# baskettarget_V2.net
KiCad netlist of a schematic drawn in EAGLE
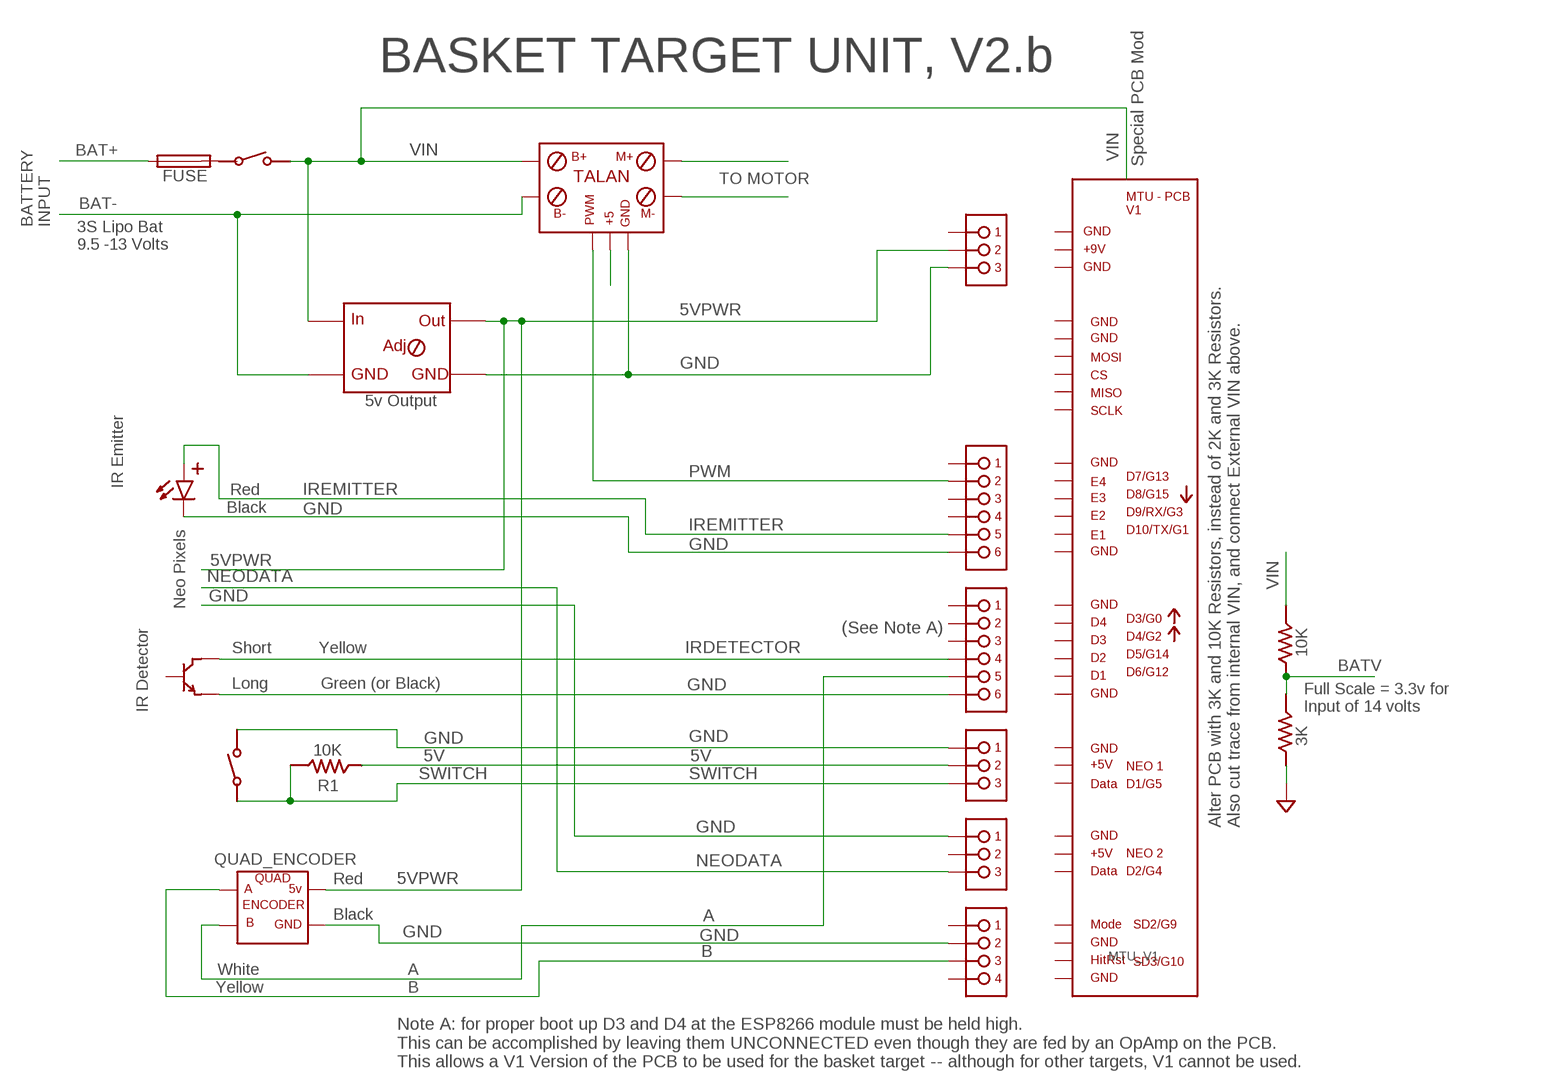
[diagram p0: schematic, sheet 1]

(export (version "E")
  (design (tool "Eeschema 10.0.6"))
  (components
    (comp (ref "F2")
      (value "FUSE")
      (footprint "eagle-import:FUSE_HOLDER_WICKMANN-19596")
      (libsource (lib "eagle-import") (part "FUSE19596"))
    )
    (comp (ref "J1")
      (value "ENCODER")
      (footprint "eagle-import:PINHDR_TH_100_1X4")
      (libsource (lib "eagle-import") (part "PINHDR_1X4TH_VERT_100"))
    )
    (comp (ref "J2")
      (value "NEO")
      (footprint "eagle-import:PINHDR_TH_100_1X3")
      (libsource (lib "eagle-import") (part "PINHDR_1X3-100"))
    )
    (comp (ref "J4")
      (value "INPUTS")
      (footprint "eagle-import:PINHDR_TH_100_1X6")
      (libsource (lib "eagle-import") (part "PINHDR_1X6-100"))
    )
    (comp (ref "J6")
      (value "OUTPUTS")
      (footprint "eagle-import:PINHDR_TH_100_1X6")
      (libsource (lib "eagle-import") (part "PINHDR_1X6-100"))
    )
    (comp (ref "J7")
      (value "PWR")
      (footprint "eagle-import:PINHDR_TH_100_1X3")
      (libsource (lib "eagle-import") (part "PINHDR_1X3-100"))
    )
    (comp (ref "J10")
      (value "SERVO")
      (footprint "eagle-import:PINHDR_TH_100_1X3")
      (libsource (lib "eagle-import") (part "PINHDR_1X3-100"))
    )
    (comp (ref "LED1")
      (value "IR Emitter")
      (footprint "eagle-import:LED-TH100")
      (libsource (lib "eagle-import") (part "LEDTH-DIP-100"))
    )
    (comp (ref "M1")
      (value "MTU_V1")
      (footprint "eagle-import:MTU_V1")
      (libsource (lib "eagle-import") (part "MTU_V1"))
    )
    (comp (ref "M2")
      (value "TALAN")
      (footprint "eagle-import:TALAN_PWM")
      (libsource (lib "eagle-import") (part "TALAN"))
    )
    (comp (ref "M4")
      (value "5v Output")
      (footprint "eagle-import:DC_DC_MODULE")
      (libsource (lib "eagle-import") (part "DC_DC_MODULE"))
    )
    (comp (ref "R1")
      (value "10K")
      (footprint "eagle-import:R300")
      (libsource (lib "eagle-import") (part "RTHOLE300"))
    )
    (comp (ref "R10")
      (value "10K")
      (footprint "eagle-import:R300")
      (libsource (lib "eagle-import") (part "RTHOLE300"))
    )
    (comp (ref "R11")
      (value "3K")
      (footprint "eagle-import:R300")
      (libsource (lib "eagle-import") (part "RTHOLE300"))
    )
    (comp (ref "S1")
      (value "TOGGLE_SPST")
      (footprint "eagle-import:SPST_TOGGLE")
      (libsource (lib "eagle-import") (part "TOGGLE_SPST"))
    )
    (comp (ref "S2")
      (value "TOGGLE_SPST")
      (footprint "eagle-import:SPST_TOGGLE")
      (libsource (lib "eagle-import") (part "TOGGLE_SPST"))
    )
    (comp (ref "T1")
      (value "T_NPN")
      (footprint "eagle-import:TO-92")
      (libsource (lib "eagle-import") (part "T_NPN"))
    )
    (comp (ref "U2")
      (value "QUAD_ENCODER")
      (footprint "eagle-import:QUAD_ENCODER")
      (libsource (lib "eagle-import") (part "QUAD_ENCODER"))
    )
  )
  (nets
    (net (code "1") (name "/5V") (class "Default")
      (node (ref "J2") (pin "2") (pinfunction "2_2") (pintype "passive"))
      (node (ref "R1") (pin "P$1") (pinfunction "1_P$1") (pintype "passive"))
    )
    (net (code "2") (name "/5VPWR") (class "Default")
      (node (ref "J7") (pin "2") (pinfunction "2_2") (pintype "passive"))
      (node (ref "M4") (pin "OUT+") (pinfunction "OUT_OUT+") (pintype "passive"))
      (node (ref "U2") (pin "5V") (pinfunction "5V_5V") (pintype "passive"))
    )
    (net (code "3") (name "/A") (class "Default")
      (node (ref "J4") (pin "5") (pinfunction "5_5") (pintype "passive"))
      (node (ref "U2") (pin "B") (pinfunction "B_B") (pintype "passive"))
    )
    (net (code "4") (name "/B") (class "Default")
      (node (ref "J1") (pin "3") (pinfunction "3_3") (pintype "passive"))
      (node (ref "U2") (pin "A") (pinfunction "A_A") (pintype "passive"))
    )
    (net (code "5") (name "/BAT+") (class "Default")
      (node (ref "F2") (pin "A") (pinfunction "1_A") (pintype "passive"))
    )
    (net (code "6") (name "/BAT-") (class "Default")
      (node (ref "M2") (pin "B-") (pinfunction "B-_B-") (pintype "passive"))
      (node (ref "M4") (pin "IN-") (pinfunction "G1_IN-") (pintype "passive"))
    )
    (net (code "7") (name "/BATV") (class "Default")
      (node (ref "R10") (pin "P$1") (pinfunction "1_P$1") (pintype "passive"))
      (node (ref "R11") (pin "P$2") (pinfunction "2_P$2") (pintype "passive"))
    )
    (net (code "8") (name "/IRDETECTOR") (class "Default")
      (node (ref "J4") (pin "4") (pinfunction "4_4") (pintype "passive"))
      (node (ref "T1") (pin "P$1") (pinfunction "COLLECTOR_P$1") (pintype "passive"))
    )
    (net (code "9") (name "/IREMITTER") (class "Default")
      (node (ref "J6") (pin "5") (pinfunction "5_5") (pintype "passive"))
      (node (ref "LED1") (pin "P$1") (pinfunction "ANODE_P$1") (pintype "passive"))
    )
    (net (code "10") (name "/NEODATA") (class "Default")
      (node (ref "J10") (pin "3") (pinfunction "3_3") (pintype "passive"))
    )
    (net (code "11") (name "/PWM") (class "Default")
      (node (ref "J6") (pin "2") (pinfunction "2_2") (pintype "passive"))
      (node (ref "M2") (pin "PWM") (pinfunction "PWM_PWM") (pintype "passive"))
    )
    (net (code "12") (name "/SWITCH") (class "Default")
      (node (ref "J2") (pin "3") (pinfunction "3_3") (pintype "passive"))
      (node (ref "R1") (pin "P$2") (pinfunction "2_P$2") (pintype "passive"))
      (node (ref "S1") (pin "P$1") (pinfunction "P$1_P$1") (pintype "passive"))
    )
    (net (code "13") (name "/VIN") (class "Default")
      (node (ref "M2") (pin "B+") (pinfunction "B+_B+") (pintype "passive"))
      (node (ref "M4") (pin "IN+") (pinfunction "IN_IN+") (pintype "passive"))
      (node (ref "R10") (pin "P$2") (pinfunction "2_P$2") (pintype "passive"))
      (node (ref "S2") (pin "P$2") (pinfunction "P$2_P$2") (pintype "passive"))
    )
    (net (code "14") (name "GND") (class "Default")
      (node (ref "J1") (pin "2") (pinfunction "2_2") (pintype "passive"))
      (node (ref "J10") (pin "1") (pinfunction "1_1") (pintype "passive"))
      (node (ref "J2") (pin "1") (pinfunction "1_1") (pintype "passive"))
      (node (ref "J4") (pin "6") (pinfunction "6_6") (pintype "passive"))
      (node (ref "J6") (pin "6") (pinfunction "6_6") (pintype "passive"))
      (node (ref "J7") (pin "3") (pinfunction "3_3") (pintype "passive"))
      (node (ref "LED1") (pin "P$2") (pinfunction "CATHODE_P$2") (pintype "passive"))
      (node (ref "M2") (pin "GND") (pinfunction "GND_GND") (pintype "passive"))
      (node (ref "M4") (pin "OUT-") (pinfunction "G2_OUT-") (pintype "passive"))
      (node (ref "R11") (pin "P$1") (pinfunction "1_P$1") (pintype "passive"))
      (node (ref "S1") (pin "P$2") (pinfunction "P$2_P$2") (pintype "passive"))
      (node (ref "T1") (pin "P$3") (pinfunction "EMITTER_P$3") (pintype "passive"))
      (node (ref "U2") (pin "GND") (pinfunction "GND_GND") (pintype "passive"))
    )
    (net (code "15") (name "Net-(F2-2)") (class "Default")
      (node (ref "F2") (pin "B") (pinfunction "2_B") (pintype "passive"))
      (node (ref "S2") (pin "P$1") (pinfunction "P$1_P$1") (pintype "passive"))
    )
    (net (code "16") (name "unconnected-(J1-Pad1)") (class "Default")
      (node (ref "J1") (pin "1") (pinfunction "1_1") (pintype "passive"))
    )
    (net (code "17") (name "unconnected-(J1-Pad4)") (class "Default")
      (node (ref "J1") (pin "4") (pinfunction "4_4") (pintype "passive"))
    )
    (net (code "18") (name "unconnected-(J4-Pad1)") (class "Default")
      (node (ref "J4") (pin "1") (pinfunction "1_1") (pintype "passive"))
    )
    (net (code "19") (name "unconnected-(J4-Pad2)") (class "Default")
      (node (ref "J4") (pin "2") (pinfunction "2_2") (pintype "passive"))
    )
    (net (code "20") (name "unconnected-(J4-Pad3)") (class "Default")
      (node (ref "J4") (pin "3") (pinfunction "3_3") (pintype "passive"))
    )
    (net (code "21") (name "unconnected-(J6-Pad1)") (class "Default")
      (node (ref "J6") (pin "1") (pinfunction "1_1") (pintype "passive"))
    )
    (net (code "22") (name "unconnected-(J6-Pad3)") (class "Default")
      (node (ref "J6") (pin "3") (pinfunction "3_3") (pintype "passive"))
    )
    (net (code "23") (name "unconnected-(J6-Pad4)") (class "Default")
      (node (ref "J6") (pin "4") (pinfunction "4_4") (pintype "passive"))
    )
    (net (code "24") (name "unconnected-(J7-Pad1)") (class "Default")
      (node (ref "J7") (pin "1") (pinfunction "1_1") (pintype "passive"))
    )
    (net (code "25") (name "unconnected-(J10-Pad2)") (class "Default")
      (node (ref "J10") (pin "2") (pinfunction "2_2") (pintype "passive"))
    )
    (net (code "26") (name "unconnected-(M1-PadP$1)") (class "Default")
      (node (ref "M1") (pin "P$1") (pinfunction "P$1_P$1") (pintype "bidirectional"))
    )
    (net (code "27") (name "unconnected-(M1-PadP$2)") (class "Default")
      (node (ref "M1") (pin "P$2") (pinfunction "P$2_P$2") (pintype "bidirectional"))
    )
    (net (code "28") (name "unconnected-(M1-PadP$3)") (class "Default")
      (node (ref "M1") (pin "P$3") (pinfunction "P$3_P$3") (pintype "bidirectional"))
    )
    (net (code "29") (name "unconnected-(M1-PadP$4)") (class "Default")
      (node (ref "M1") (pin "P$4") (pinfunction "P$4_P$4") (pintype "bidirectional"))
    )
    (net (code "30") (name "unconnected-(M1-PadP$5)") (class "Default")
      (node (ref "M1") (pin "P$5") (pinfunction "P$5_P$5") (pintype "bidirectional"))
    )
    (net (code "31") (name "unconnected-(M1-PadP$6)") (class "Default")
      (node (ref "M1") (pin "P$6") (pinfunction "P$6_P$6") (pintype "bidirectional"))
    )
    (net (code "32") (name "unconnected-(M1-PadP$7)") (class "Default")
      (node (ref "M1") (pin "P$7") (pinfunction "P$7_P$7") (pintype "bidirectional"))
    )
    (net (code "33") (name "unconnected-(M1-PadP$8)") (class "Default")
      (node (ref "M1") (pin "P$8") (pinfunction "P$8_P$8") (pintype "bidirectional"))
    )
    (net (code "34") (name "unconnected-(M1-PadP$9)") (class "Default")
      (node (ref "M1") (pin "P$9") (pinfunction "P$9_P$9") (pintype "bidirectional"))
    )
    (net (code "35") (name "unconnected-(M1-PadP$10)") (class "Default")
      (node (ref "M1") (pin "P$10") (pinfunction "P$10_P$10") (pintype "bidirectional"))
    )
    (net (code "36") (name "unconnected-(M1-PadP$11)") (class "Default")
      (node (ref "M1") (pin "P$11") (pinfunction "P$11_P$11") (pintype "bidirectional"))
    )
    (net (code "37") (name "unconnected-(M1-PadP$12)") (class "Default")
      (node (ref "M1") (pin "P$12") (pinfunction "P$12_P$12") (pintype "bidirectional"))
    )
    (net (code "38") (name "unconnected-(M1-PadP$13)") (class "Default")
      (node (ref "M1") (pin "P$13") (pinfunction "P$13_P$13") (pintype "bidirectional"))
    )
    (net (code "39") (name "unconnected-(M1-PadP$14)") (class "Default")
      (node (ref "M1") (pin "P$14") (pinfunction "P$14_P$14") (pintype "bidirectional"))
    )
    (net (code "40") (name "unconnected-(M1-PadP$15)") (class "Default")
      (node (ref "M1") (pin "P$15") (pinfunction "P$15_P$15") (pintype "bidirectional"))
    )
    (net (code "41") (name "unconnected-(M1-PadP$16)") (class "Default")
      (node (ref "M1") (pin "P$16") (pinfunction "P$16_P$16") (pintype "bidirectional"))
    )
    (net (code "42") (name "unconnected-(M1-PadP$17)") (class "Default")
      (node (ref "M1") (pin "P$17") (pinfunction "P$17_P$17") (pintype "bidirectional"))
    )
    (net (code "43") (name "unconnected-(M1-PadP$18)") (class "Default")
      (node (ref "M1") (pin "P$18") (pinfunction "P$18_P$18") (pintype "bidirectional"))
    )
    (net (code "44") (name "unconnected-(M1-PadP$19)") (class "Default")
      (node (ref "M1") (pin "P$19") (pinfunction "P$19_P$19") (pintype "bidirectional"))
    )
    (net (code "45") (name "unconnected-(M1-PadP$20)") (class "Default")
      (node (ref "M1") (pin "P$20") (pinfunction "P$20_P$20") (pintype "bidirectional"))
    )
    (net (code "46") (name "unconnected-(M1-PadP$21)") (class "Default")
      (node (ref "M1") (pin "P$21") (pinfunction "P$21_P$21") (pintype "bidirectional"))
    )
    (net (code "47") (name "unconnected-(M1-PadP$22)") (class "Default")
      (node (ref "M1") (pin "P$22") (pinfunction "P$22_P$22") (pintype "bidirectional"))
    )
    (net (code "48") (name "unconnected-(M1-PadP$23)") (class "Default")
      (node (ref "M1") (pin "P$23") (pinfunction "P$23_P$23") (pintype "bidirectional"))
    )
    (net (code "49") (name "unconnected-(M1-PadP$24)") (class "Default")
      (node (ref "M1") (pin "P$24") (pinfunction "P$24_P$24") (pintype "bidirectional"))
    )
    (net (code "50") (name "unconnected-(M1-PadP$25)") (class "Default")
      (node (ref "M1") (pin "P$25") (pinfunction "P$25_P$25") (pintype "bidirectional"))
    )
    (net (code "51") (name "unconnected-(M1-PadP$26)") (class "Default")
      (node (ref "M1") (pin "P$26") (pinfunction "P$26_P$26") (pintype "bidirectional"))
    )
    (net (code "52") (name "unconnected-(M1-PadP$27)") (class "Default")
      (node (ref "M1") (pin "P$27") (pinfunction "P$27_P$27") (pintype "bidirectional"))
    )
    (net (code "53") (name "unconnected-(M1-PadP$28)") (class "Default")
      (node (ref "M1") (pin "P$28") (pinfunction "P$28_P$28") (pintype "bidirectional"))
    )
    (net (code "54") (name "unconnected-(M1-PadP$29)") (class "Default")
      (node (ref "M1") (pin "P$29") (pinfunction "P$29_P$29") (pintype "bidirectional"))
    )
    (net (code "55") (name "unconnected-(M1-PadP$30)") (class "Default")
      (node (ref "M1") (pin "P$30") (pinfunction "P$30_P$30") (pintype "bidirectional"))
    )
    (net (code "56") (name "unconnected-(M1-PadP$31)") (class "Default")
      (node (ref "M1") (pin "P$31") (pinfunction "P$31_P$31") (pintype "bidirectional"))
    )
    (net (code "57") (name "unconnected-(M2-Pad5V)") (class "Default")
      (node (ref "M2") (pin "5V") (pinfunction "5V_5V") (pintype "passive"))
    )
    (net (code "58") (name "unconnected-(M2-PadM+)") (class "Default")
      (node (ref "M2") (pin "M+") (pinfunction "M+_M+") (pintype "passive"))
    )
    (net (code "59") (name "unconnected-(M2-PadM-)") (class "Default")
      (node (ref "M2") (pin "M-") (pinfunction "M-_M-") (pintype "passive"))
    )
    (net (code "60") (name "unconnected-(T1-BASE-PadP$2)") (class "Default")
      (node (ref "T1") (pin "P$2") (pinfunction "BASE_P$2") (pintype "passive"))
    )
  )
)
